# Wireless_Shiled.net
KiCad netlist of a schematic drawn in Altium Designer
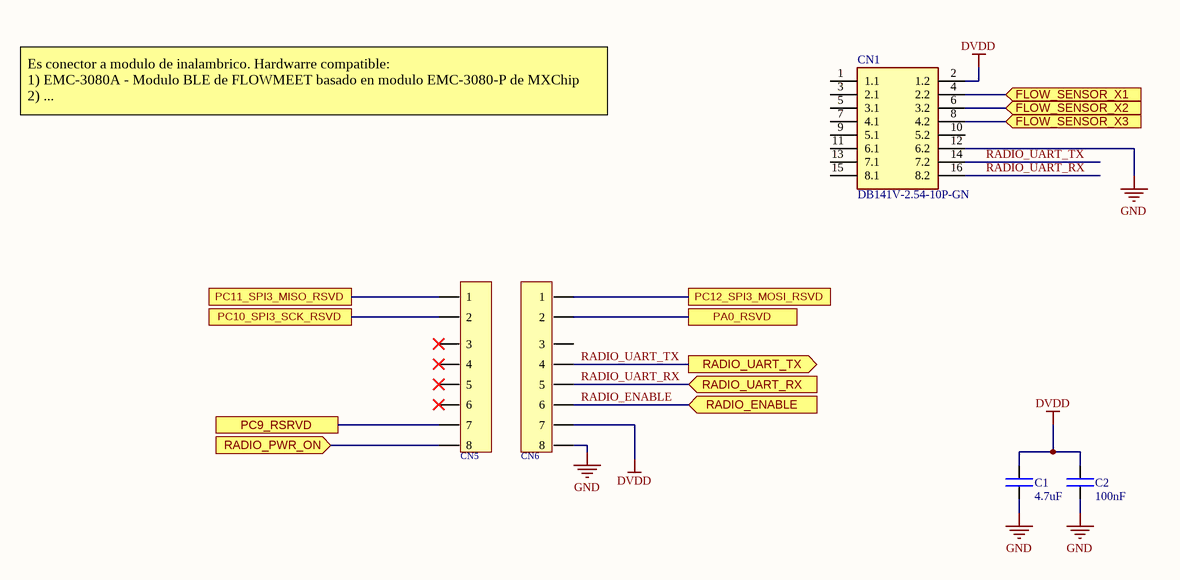
[diagram p0: Wireless_Shiled.SchDoc]

(export (version "E")
  (design (tool "Eeschema 10.0.6"))
  (components
    (comp (ref "C1")
      (value "4.7uF")
      (footprint "CAP_SM0603_YAGEOCC2_N")
      (description "CAP 4.7uF SM0603 X7R 16V YAGEO")
      (fields
        (field (name "MANUFACTURER") "Yageo")
        (field (name "MANUFACTURER PART NUMBER") "CC0603JRX7R7BB473")
      )
      (libsource (lib "yageo") (part "CC0603KRX5R6BB475"))
    )
    (comp (ref "C2")
      (value "100nF")
      (footprint "CAP_SM0603_YAGEOCC2_N")
      (description "CAP 100nF SM0603 X7R 50V YAGEO CC2")
      (fields
        (field (name "MANUFACTURER") "Yageo")
        (field (name "MANUFACTURER PART NUMBER") "CC0603KRX7R9BB104")
      )
      (libsource (lib "yageo") (part "CC0603KRX7R9BB104"))
    )
    (comp (ref "CN1")
      (value "DB141V-2.54-10P-GN")
      (footprint "SHDR16W90P508X254_2X8_2282X1260X1375P")
      (fields (field (name "MANUFACTURER") "Dorabo") (field (name "VENDOR PART NUMBER") "C2898752"))
      (libsource (lib "flowmeet") (part "DB141V-2.54-10P-GN"))
    )
    (comp (ref "CN5")
      (value "DW200R-11-08-43")
      (footprint "DW200R-11-08-43")
      (description "1 x 8 - tru hole 2mm - altura 4.3mm")
      (fields (field (name "MANUFACTURER") "Dealon"))
      (libsource (lib "") (part "DW200R-11-08-43_1"))
    )
    (comp (ref "CN6")
      (value "DW200R-11-08-43")
      (footprint "DW200R-11-08-43")
      (description "1 x 8 - tru hole 2mm - altura 4.3mm")
      (fields (field (name "MANUFACTURER") "Dealon"))
      (libsource (lib "flowmeet") (part "DW200R-11-08-43"))
    )
  )
  (nets
    (net (code "1") (name "/FLOW_SENSOR_X1") (class "Default")
      (node (ref "CN1") (pin "4") (pinfunction "2.2_4") (pintype "passive"))
    )
    (net (code "2") (name "/FLOW_SENSOR_X2") (class "Default")
      (node (ref "CN1") (pin "6") (pinfunction "3.2_6") (pintype "passive"))
    )
    (net (code "3") (name "/FLOW_SENSOR_X3") (class "Default")
      (node (ref "CN1") (pin "8") (pinfunction "4.2_8") (pintype "passive"))
    )
    (net (code "4") (name "/PA0_RSVD") (class "Default")
      (node (ref "CN6") (pin "2") (pinfunction "2_2") (pintype "passive"))
    )
    (net (code "5") (name "/PC9_RSRVD") (class "Default")
      (node (ref "CN5") (pin "7") (pinfunction "7_7") (pintype "passive"))
    )
    (net (code "6") (name "/PC10_SPI3_SCK_RSVD") (class "Default")
      (node (ref "CN5") (pin "2") (pinfunction "2_2") (pintype "passive"))
    )
    (net (code "7") (name "/PC11_SPI3_MISO_RSVD") (class "Default")
      (node (ref "CN5") (pin "1") (pinfunction "1_1") (pintype "passive"))
    )
    (net (code "8") (name "/PC12_SPI3_MOSI_RSVD") (class "Default")
      (node (ref "CN6") (pin "1") (pinfunction "1_1") (pintype "passive"))
    )
    (net (code "9") (name "/RADIO_ENABLE") (class "Default")
      (node (ref "CN6") (pin "6") (pinfunction "6_6") (pintype "passive"))
    )
    (net (code "10") (name "/RADIO_PWR_ON") (class "Default")
      (node (ref "CN5") (pin "8") (pinfunction "8_8") (pintype "passive"))
    )
    (net (code "11") (name "/RADIO_UART_RX") (class "Default")
      (node (ref "CN1") (pin "16") (pinfunction "8.2_16") (pintype "passive"))
      (node (ref "CN6") (pin "5") (pinfunction "5_5") (pintype "passive"))
    )
    (net (code "12") (name "/RADIO_UART_TX") (class "Default")
      (node (ref "CN1") (pin "14") (pinfunction "7.2_14") (pintype "passive"))
      (node (ref "CN6") (pin "4") (pinfunction "4_4") (pintype "passive"))
    )
    (net (code "13") (name "DVDD") (class "Default")
      (node (ref "C1") (pin "1") (pintype "passive"))
      (node (ref "C2") (pin "1") (pintype "passive"))
      (node (ref "CN1") (pin "2") (pinfunction "1.2_2") (pintype "passive"))
      (node (ref "CN6") (pin "7") (pinfunction "7_7") (pintype "passive"))
    )
    (net (code "14") (name "GND") (class "Default")
      (node (ref "C1") (pin "2") (pintype "passive"))
      (node (ref "C2") (pin "2") (pintype "passive"))
      (node (ref "CN1") (pin "12") (pinfunction "6.2_12") (pintype "passive"))
      (node (ref "CN6") (pin "8") (pinfunction "8_8") (pintype "passive"))
    )
    (net (code "15") (name "unconnected-(CN1-1.1-Pad1)") (class "Default")
      (node (ref "CN1") (pin "1") (pinfunction "1.1_1") (pintype "passive"))
    )
    (net (code "16") (name "unconnected-(CN1-2.1-Pad3)") (class "Default")
      (node (ref "CN1") (pin "3") (pinfunction "2.1_3") (pintype "passive"))
    )
    (net (code "17") (name "unconnected-(CN1-3.1-Pad5)") (class "Default")
      (node (ref "CN1") (pin "5") (pinfunction "3.1_5") (pintype "passive"))
    )
    (net (code "18") (name "unconnected-(CN1-4.1-Pad7)") (class "Default")
      (node (ref "CN1") (pin "7") (pinfunction "4.1_7") (pintype "passive"))
    )
    (net (code "19") (name "unconnected-(CN1-5.1-Pad9)") (class "Default")
      (node (ref "CN1") (pin "9") (pinfunction "5.1_9") (pintype "passive"))
    )
    (net (code "20") (name "unconnected-(CN1-5.2-Pad10)") (class "Default")
      (node (ref "CN1") (pin "10") (pinfunction "5.2_10") (pintype "passive"))
    )
    (net (code "21") (name "unconnected-(CN1-6.1-Pad11)") (class "Default")
      (node (ref "CN1") (pin "11") (pinfunction "6.1_11") (pintype "passive"))
    )
    (net (code "22") (name "unconnected-(CN1-7.1-Pad13)") (class "Default")
      (node (ref "CN1") (pin "13") (pinfunction "7.1_13") (pintype "passive"))
    )
    (net (code "23") (name "unconnected-(CN1-8.1-Pad15)") (class "Default")
      (node (ref "CN1") (pin "15") (pinfunction "8.1_15") (pintype "passive"))
    )
    (net (code "24") (name "unconnected-(CN5-Pad3)") (class "Default")
      (node (ref "CN5") (pin "3") (pinfunction "3_3") (pintype "passive+no_connect"))
    )
    (net (code "25") (name "unconnected-(CN5-Pad4)") (class "Default")
      (node (ref "CN5") (pin "4") (pinfunction "4_4") (pintype "passive+no_connect"))
    )
    (net (code "26") (name "unconnected-(CN5-Pad5)") (class "Default")
      (node (ref "CN5") (pin "5") (pinfunction "5_5") (pintype "passive+no_connect"))
    )
    (net (code "27") (name "unconnected-(CN5-Pad6)") (class "Default")
      (node (ref "CN5") (pin "6") (pinfunction "6_6") (pintype "passive+no_connect"))
    )
    (net (code "28") (name "unconnected-(CN6-Pad3)") (class "Default")
      (node (ref "CN6") (pin "3") (pinfunction "3_3") (pintype "passive"))
    )
  )
)
